# lp_port_tester.net
KiCad netlist of a schematic drawn in EAGLE
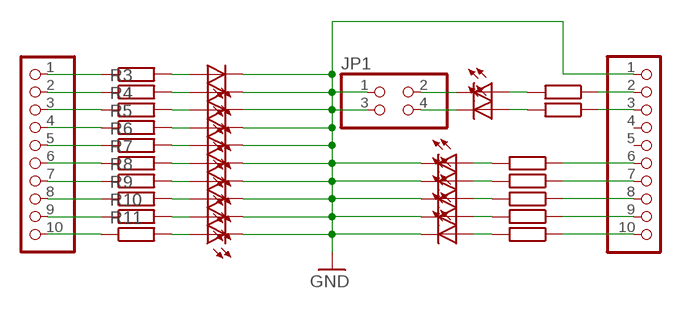
[diagram p0: schematic, sheet 1]

(export (version "E")
  (design (tool "Eeschema 10.0.6"))
  (components
    (comp (ref "J1")
      (value "J1")
      (footprint "eagle-import:1X10")
      (libsource (lib "eagle-import") (part "PINHD-1X10"))
    )
    (comp (ref "J2")
      (value "J2")
      (footprint "eagle-import:1X10")
      (libsource (lib "eagle-import") (part "PINHD-1X10"))
    )
    (comp (ref "JP1")
      (value "PINHD-2X2")
      (footprint "eagle-import:2X02")
      (libsource (lib "eagle-import") (part "PINHD-2X2"))
    )
    (comp (ref "PWR")
      (value "PWR")
      (footprint "eagle-import:CHIPLED_1206")
      (libsource (lib "eagle-import") (part "LEDCHIPLED_1206"))
    )
    (comp (ref "PWR1")
      (value "PWR")
      (footprint "eagle-import:CHIPLED_1206")
      (libsource (lib "eagle-import") (part "LEDCHIPLED_1206"))
    )
    (comp (ref "PWR2")
      (value "PWR")
      (footprint "eagle-import:CHIPLED_1206")
      (libsource (lib "eagle-import") (part "LEDCHIPLED_1206"))
    )
    (comp (ref "PWR3")
      (value "PWR")
      (footprint "eagle-import:CHIPLED_1206")
      (libsource (lib "eagle-import") (part "LEDCHIPLED_1206"))
    )
    (comp (ref "PWR4")
      (value "PWR")
      (footprint "eagle-import:CHIPLED_1206")
      (libsource (lib "eagle-import") (part "LEDCHIPLED_1206"))
    )
    (comp (ref "PWR5")
      (value "PWR")
      (footprint "eagle-import:CHIPLED_1206")
      (libsource (lib "eagle-import") (part "LEDCHIPLED_1206"))
    )
    (comp (ref "PWR6")
      (value "PWR")
      (footprint "eagle-import:CHIPLED_1206")
      (libsource (lib "eagle-import") (part "LEDCHIPLED_1206"))
    )
    (comp (ref "PWR7")
      (value "PWR")
      (footprint "eagle-import:CHIPLED_1206")
      (libsource (lib "eagle-import") (part "LEDCHIPLED_1206"))
    )
    (comp (ref "PWR8")
      (value "PWR")
      (footprint "eagle-import:CHIPLED_1206")
      (libsource (lib "eagle-import") (part "LEDCHIPLED_1206"))
    )
    (comp (ref "PWR9")
      (value "PWR")
      (footprint "eagle-import:CHIPLED_1206")
      (libsource (lib "eagle-import") (part "LEDCHIPLED_1206"))
    )
    (comp (ref "PWR10")
      (value "PWR")
      (footprint "eagle-import:CHIPLED_1206")
      (libsource (lib "eagle-import") (part "LEDCHIPLED_1206"))
    )
    (comp (ref "PWR11")
      (value "PWR")
      (footprint "eagle-import:CHIPLED_1206")
      (libsource (lib "eagle-import") (part "LEDCHIPLED_1206"))
    )
    (comp (ref "PWR14")
      (value "PWR")
      (footprint "eagle-import:CHIPLED_1206")
      (libsource (lib "eagle-import") (part "LEDCHIPLED_1206"))
    )
    (comp (ref "PWR15")
      (value "PWR")
      (footprint "eagle-import:CHIPLED_1206")
      (libsource (lib "eagle-import") (part "LEDCHIPLED_1206"))
    )
    (comp (ref "PWR16")
      (value "PWR")
      (footprint "eagle-import:CHIPLED_1206")
      (libsource (lib "eagle-import") (part "LEDCHIPLED_1206"))
    )
    (comp (ref "PWR17")
      (value "PWR")
      (footprint "eagle-import:CHIPLED_1206")
      (libsource (lib "eagle-import") (part "LEDCHIPLED_1206"))
    )
    (comp (ref "PWR18")
      (value "PWR")
      (footprint "eagle-import:CHIPLED_1206")
      (libsource (lib "eagle-import") (part "LEDCHIPLED_1206"))
    )
    (comp (ref "R1")
      (value "470")
      (footprint "eagle-import:R0805")
      (libsource (lib "eagle-import") (part "R-EU_R0805"))
    )
    (comp (ref "R2")
      (value "470")
      (footprint "eagle-import:R0805")
      (libsource (lib "eagle-import") (part "R-EU_R0805"))
    )
    (comp (ref "R3")
      (value "470")
      (footprint "eagle-import:R0805")
      (libsource (lib "eagle-import") (part "R-EU_R0805"))
    )
    (comp (ref "R4")
      (value "470")
      (footprint "eagle-import:R0805")
      (libsource (lib "eagle-import") (part "R-EU_R0805"))
    )
    (comp (ref "R5")
      (value "470")
      (footprint "eagle-import:R0805")
      (libsource (lib "eagle-import") (part "R-EU_R0805"))
    )
    (comp (ref "R6")
      (value "470")
      (footprint "eagle-import:R0805")
      (libsource (lib "eagle-import") (part "R-EU_R0805"))
    )
    (comp (ref "R7")
      (value "470")
      (footprint "eagle-import:R0805")
      (libsource (lib "eagle-import") (part "R-EU_R0805"))
    )
    (comp (ref "R8")
      (value "470")
      (footprint "eagle-import:R0805")
      (libsource (lib "eagle-import") (part "R-EU_R0805"))
    )
    (comp (ref "R9")
      (value "470")
      (footprint "eagle-import:R0805")
      (libsource (lib "eagle-import") (part "R-EU_R0805"))
    )
    (comp (ref "R10")
      (value "470")
      (footprint "eagle-import:R0805")
      (libsource (lib "eagle-import") (part "R-EU_R0805"))
    )
    (comp (ref "R11")
      (value "470")
      (footprint "eagle-import:R0805")
      (libsource (lib "eagle-import") (part "R-EU_R0805"))
    )
    (comp (ref "R12")
      (value "470")
      (footprint "eagle-import:R0805")
      (libsource (lib "eagle-import") (part "R-EU_R0805"))
    )
    (comp (ref "R15")
      (value "470")
      (footprint "eagle-import:R0805")
      (libsource (lib "eagle-import") (part "R-EU_R0805"))
    )
    (comp (ref "R16")
      (value "470")
      (footprint "eagle-import:R0805")
      (libsource (lib "eagle-import") (part "R-EU_R0805"))
    )
    (comp (ref "R17")
      (value "470")
      (footprint "eagle-import:R0805")
      (libsource (lib "eagle-import") (part "R-EU_R0805"))
    )
    (comp (ref "R18")
      (value "470")
      (footprint "eagle-import:R0805")
      (libsource (lib "eagle-import") (part "R-EU_R0805"))
    )
    (comp (ref "R19")
      (value "470")
      (footprint "eagle-import:R0805")
      (libsource (lib "eagle-import") (part "R-EU_R0805"))
    )
  )
  (nets
    (net (code "1") (name "GND") (class "Default")
      (node (ref "J2") (pin "1") (pinfunction "1_1") (pintype "passive"))
      (node (ref "JP1") (pin "1") (pinfunction "1_1") (pintype "passive"))
      (node (ref "JP1") (pin "3") (pinfunction "3_3") (pintype "passive"))
      (node (ref "PWR1") (pin "C") (pinfunction "C_C") (pintype "passive"))
      (node (ref "PWR10") (pin "C") (pinfunction "C_C") (pintype "passive"))
      (node (ref "PWR14") (pin "C") (pinfunction "C_C") (pintype "passive"))
      (node (ref "PWR15") (pin "C") (pinfunction "C_C") (pintype "passive"))
      (node (ref "PWR16") (pin "C") (pinfunction "C_C") (pintype "passive"))
      (node (ref "PWR17") (pin "C") (pinfunction "C_C") (pintype "passive"))
      (node (ref "PWR18") (pin "C") (pinfunction "C_C") (pintype "passive"))
      (node (ref "PWR2") (pin "C") (pinfunction "C_C") (pintype "passive"))
      (node (ref "PWR3") (pin "C") (pinfunction "C_C") (pintype "passive"))
      (node (ref "PWR4") (pin "C") (pinfunction "C_C") (pintype "passive"))
      (node (ref "PWR5") (pin "C") (pinfunction "C_C") (pintype "passive"))
      (node (ref "PWR6") (pin "C") (pinfunction "C_C") (pintype "passive"))
      (node (ref "PWR7") (pin "C") (pinfunction "C_C") (pintype "passive"))
      (node (ref "PWR8") (pin "C") (pinfunction "C_C") (pintype "passive"))
      (node (ref "PWR9") (pin "C") (pinfunction "C_C") (pintype "passive"))
    )
    (net (code "2") (name "Net-(J1-Pad1)") (class "Default")
      (node (ref "J1") (pin "1") (pinfunction "1_1") (pintype "passive"))
      (node (ref "R1") (pin "1") (pinfunction "1_1") (pintype "passive"))
    )
    (net (code "3") (name "Net-(J1-Pad2)") (class "Default")
      (node (ref "J1") (pin "2") (pinfunction "2_2") (pintype "passive"))
      (node (ref "R3") (pin "1") (pinfunction "1_1") (pintype "passive"))
    )
    (net (code "4") (name "Net-(J1-Pad3)") (class "Default")
      (node (ref "J1") (pin "3") (pinfunction "3_3") (pintype "passive"))
      (node (ref "R4") (pin "1") (pinfunction "1_1") (pintype "passive"))
    )
    (net (code "5") (name "Net-(J1-Pad4)") (class "Default")
      (node (ref "J1") (pin "4") (pinfunction "4_4") (pintype "passive"))
      (node (ref "R5") (pin "1") (pinfunction "1_1") (pintype "passive"))
    )
    (net (code "6") (name "Net-(J1-Pad5)") (class "Default")
      (node (ref "J1") (pin "5") (pinfunction "5_5") (pintype "passive"))
      (node (ref "R6") (pin "1") (pinfunction "1_1") (pintype "passive"))
    )
    (net (code "7") (name "Net-(J1-Pad6)") (class "Default")
      (node (ref "J1") (pin "6") (pinfunction "6_6") (pintype "passive"))
      (node (ref "R7") (pin "1") (pinfunction "1_1") (pintype "passive"))
    )
    (net (code "8") (name "Net-(J1-Pad7)") (class "Default")
      (node (ref "J1") (pin "7") (pinfunction "7_7") (pintype "passive"))
      (node (ref "R8") (pin "1") (pinfunction "1_1") (pintype "passive"))
    )
    (net (code "9") (name "Net-(J1-Pad8)") (class "Default")
      (node (ref "J1") (pin "8") (pinfunction "8_8") (pintype "passive"))
      (node (ref "R9") (pin "1") (pinfunction "1_1") (pintype "passive"))
    )
    (net (code "10") (name "Net-(J1-Pad9)") (class "Default")
      (node (ref "J1") (pin "9") (pinfunction "9_9") (pintype "passive"))
      (node (ref "R10") (pin "1") (pinfunction "1_1") (pintype "passive"))
    )
    (net (code "11") (name "Net-(J1-Pad10)") (class "Default")
      (node (ref "J1") (pin "10") (pinfunction "10_10") (pintype "passive"))
      (node (ref "R11") (pin "1") (pinfunction "1_1") (pintype "passive"))
    )
    (net (code "12") (name "Net-(J2-Pad2)") (class "Default")
      (node (ref "J2") (pin "2") (pinfunction "2_2") (pintype "passive"))
      (node (ref "R2") (pin "1") (pinfunction "1_1") (pintype "passive"))
    )
    (net (code "13") (name "Net-(J2-Pad3)") (class "Default")
      (node (ref "J2") (pin "3") (pinfunction "3_3") (pintype "passive"))
      (node (ref "R12") (pin "1") (pinfunction "1_1") (pintype "passive"))
    )
    (net (code "14") (name "Net-(J2-Pad6)") (class "Default")
      (node (ref "J2") (pin "6") (pinfunction "6_6") (pintype "passive"))
      (node (ref "R15") (pin "1") (pinfunction "1_1") (pintype "passive"))
    )
    (net (code "15") (name "Net-(J2-Pad7)") (class "Default")
      (node (ref "J2") (pin "7") (pinfunction "7_7") (pintype "passive"))
      (node (ref "R16") (pin "1") (pinfunction "1_1") (pintype "passive"))
    )
    (net (code "16") (name "Net-(J2-Pad8)") (class "Default")
      (node (ref "J2") (pin "8") (pinfunction "8_8") (pintype "passive"))
      (node (ref "R17") (pin "1") (pinfunction "1_1") (pintype "passive"))
    )
    (net (code "17") (name "Net-(J2-Pad9)") (class "Default")
      (node (ref "J2") (pin "9") (pinfunction "9_9") (pintype "passive"))
      (node (ref "R18") (pin "1") (pinfunction "1_1") (pintype "passive"))
    )
    (net (code "18") (name "Net-(J2-Pad10)") (class "Default")
      (node (ref "J2") (pin "10") (pinfunction "10_10") (pintype "passive"))
      (node (ref "R19") (pin "1") (pinfunction "1_1") (pintype "passive"))
    )
    (net (code "19") (name "Net-(JP1-Pad2)") (class "Default")
      (node (ref "JP1") (pin "2") (pinfunction "2_2") (pintype "passive"))
      (node (ref "PWR") (pin "C") (pinfunction "C_C") (pintype "passive"))
    )
    (net (code "20") (name "Net-(JP1-Pad4)") (class "Default")
      (node (ref "JP1") (pin "4") (pinfunction "4_4") (pintype "passive"))
      (node (ref "PWR11") (pin "C") (pinfunction "C_C") (pintype "passive"))
    )
    (net (code "21") (name "Net-(PWR-PadA)") (class "Default")
      (node (ref "PWR") (pin "A") (pinfunction "A_A") (pintype "passive"))
      (node (ref "R2") (pin "2") (pinfunction "2_2") (pintype "passive"))
    )
    (net (code "22") (name "Net-(PWR1-PadA)") (class "Default")
      (node (ref "PWR1") (pin "A") (pinfunction "A_A") (pintype "passive"))
      (node (ref "R1") (pin "2") (pinfunction "2_2") (pintype "passive"))
    )
    (net (code "23") (name "Net-(PWR2-PadA)") (class "Default")
      (node (ref "PWR2") (pin "A") (pinfunction "A_A") (pintype "passive"))
      (node (ref "R3") (pin "2") (pinfunction "2_2") (pintype "passive"))
    )
    (net (code "24") (name "Net-(PWR3-PadA)") (class "Default")
      (node (ref "PWR3") (pin "A") (pinfunction "A_A") (pintype "passive"))
      (node (ref "R4") (pin "2") (pinfunction "2_2") (pintype "passive"))
    )
    (net (code "25") (name "Net-(PWR4-PadA)") (class "Default")
      (node (ref "PWR4") (pin "A") (pinfunction "A_A") (pintype "passive"))
      (node (ref "R5") (pin "2") (pinfunction "2_2") (pintype "passive"))
    )
    (net (code "26") (name "Net-(PWR5-PadA)") (class "Default")
      (node (ref "PWR5") (pin "A") (pinfunction "A_A") (pintype "passive"))
      (node (ref "R6") (pin "2") (pinfunction "2_2") (pintype "passive"))
    )
    (net (code "27") (name "Net-(PWR6-PadA)") (class "Default")
      (node (ref "PWR6") (pin "A") (pinfunction "A_A") (pintype "passive"))
      (node (ref "R7") (pin "2") (pinfunction "2_2") (pintype "passive"))
    )
    (net (code "28") (name "Net-(PWR7-PadA)") (class "Default")
      (node (ref "PWR7") (pin "A") (pinfunction "A_A") (pintype "passive"))
      (node (ref "R8") (pin "2") (pinfunction "2_2") (pintype "passive"))
    )
    (net (code "29") (name "Net-(PWR8-PadA)") (class "Default")
      (node (ref "PWR8") (pin "A") (pinfunction "A_A") (pintype "passive"))
      (node (ref "R9") (pin "2") (pinfunction "2_2") (pintype "passive"))
    )
    (net (code "30") (name "Net-(PWR9-PadA)") (class "Default")
      (node (ref "PWR9") (pin "A") (pinfunction "A_A") (pintype "passive"))
      (node (ref "R10") (pin "2") (pinfunction "2_2") (pintype "passive"))
    )
    (net (code "31") (name "Net-(PWR10-PadA)") (class "Default")
      (node (ref "PWR10") (pin "A") (pinfunction "A_A") (pintype "passive"))
      (node (ref "R11") (pin "2") (pinfunction "2_2") (pintype "passive"))
    )
    (net (code "32") (name "Net-(PWR11-PadA)") (class "Default")
      (node (ref "PWR11") (pin "A") (pinfunction "A_A") (pintype "passive"))
      (node (ref "R12") (pin "2") (pinfunction "2_2") (pintype "passive"))
    )
    (net (code "33") (name "Net-(PWR14-PadA)") (class "Default")
      (node (ref "PWR14") (pin "A") (pinfunction "A_A") (pintype "passive"))
      (node (ref "R15") (pin "2") (pinfunction "2_2") (pintype "passive"))
    )
    (net (code "34") (name "Net-(PWR15-PadA)") (class "Default")
      (node (ref "PWR15") (pin "A") (pinfunction "A_A") (pintype "passive"))
      (node (ref "R16") (pin "2") (pinfunction "2_2") (pintype "passive"))
    )
    (net (code "35") (name "Net-(PWR16-PadA)") (class "Default")
      (node (ref "PWR16") (pin "A") (pinfunction "A_A") (pintype "passive"))
      (node (ref "R17") (pin "2") (pinfunction "2_2") (pintype "passive"))
    )
    (net (code "36") (name "Net-(PWR17-PadA)") (class "Default")
      (node (ref "PWR17") (pin "A") (pinfunction "A_A") (pintype "passive"))
      (node (ref "R18") (pin "2") (pinfunction "2_2") (pintype "passive"))
    )
    (net (code "37") (name "Net-(PWR18-PadA)") (class "Default")
      (node (ref "PWR18") (pin "A") (pinfunction "A_A") (pintype "passive"))
      (node (ref "R19") (pin "2") (pinfunction "2_2") (pintype "passive"))
    )
    (net (code "38") (name "unconnected-(J2-Pad4)") (class "Default")
      (node (ref "J2") (pin "4") (pinfunction "4_4") (pintype "passive"))
    )
    (net (code "39") (name "unconnected-(J2-Pad5)") (class "Default")
      (node (ref "J2") (pin "5") (pinfunction "5_5") (pintype "passive"))
    )
  )
)
